# BIT_5.net
KiCad netlist of a schematic drawn in EasyEDA
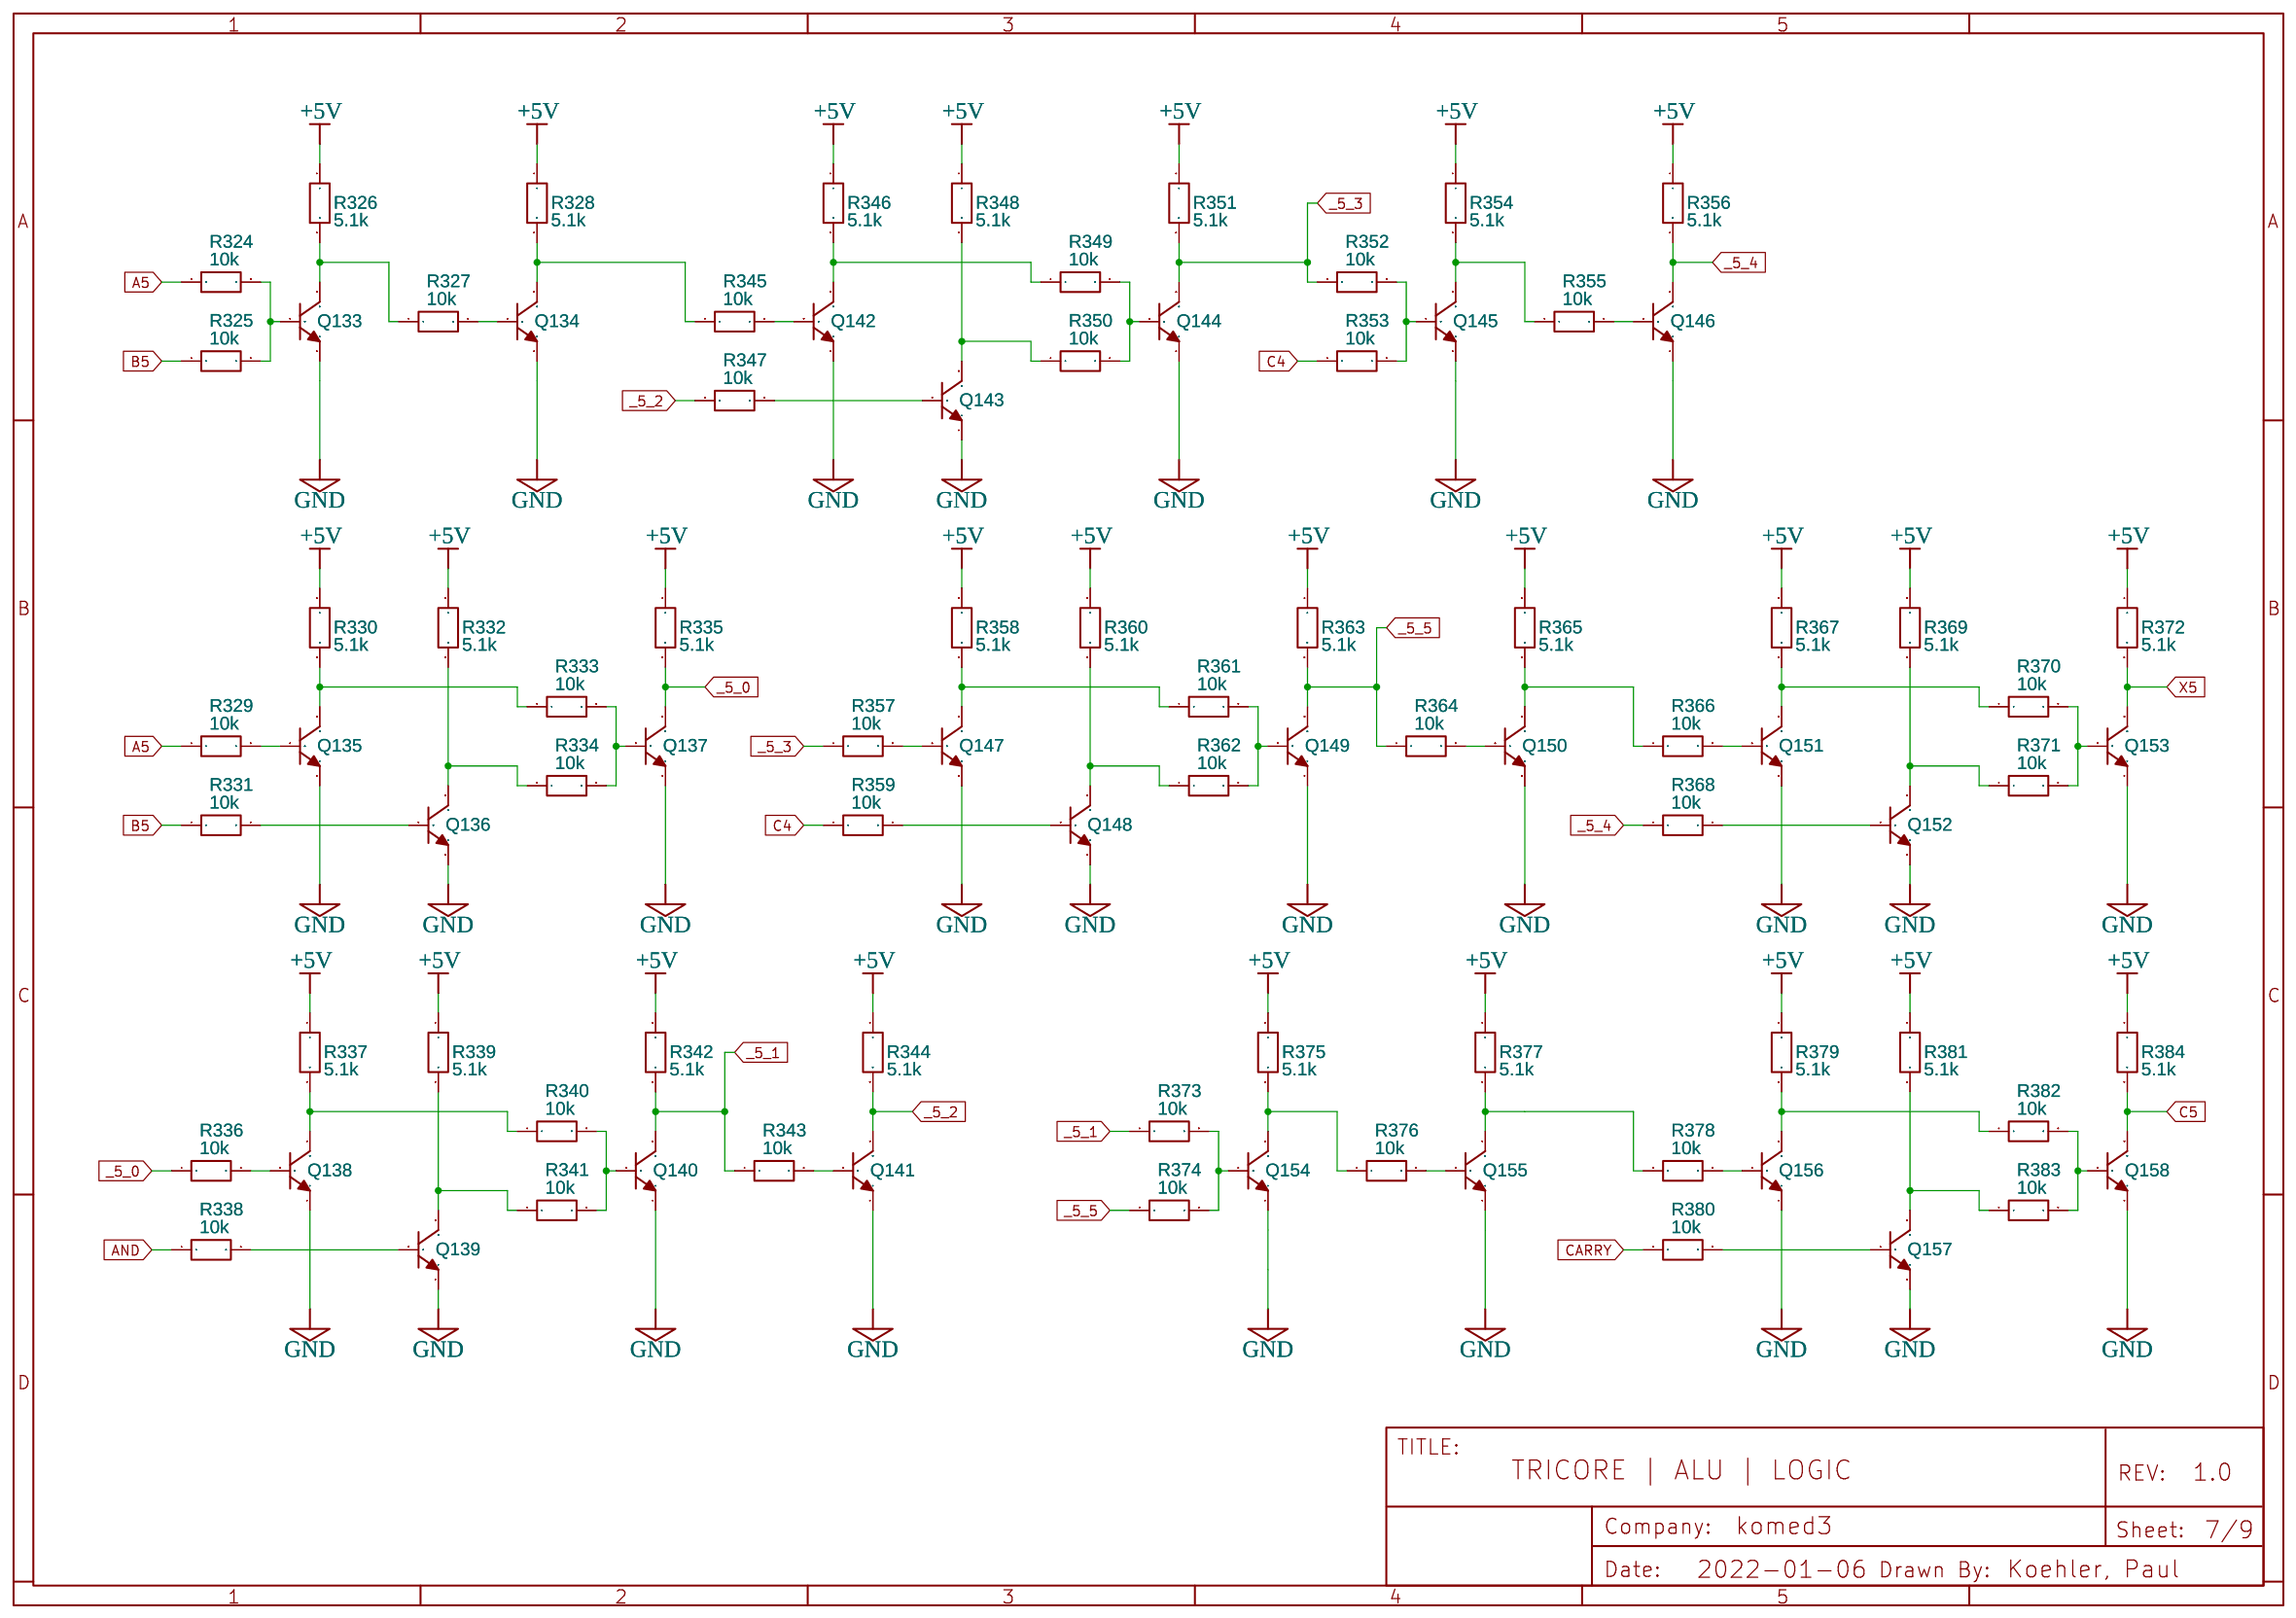
[diagram p0: schematic sheet]

(export (version "E")
  (design (tool "Eeschema 10.0.6"))
  (components
    (comp (ref "Q133")
      (value "2N3904(TO-92)")
      (fields (field (name "BOM_Manufacturer Part") "2N3904") (field (name "BOM_Supplier Part") "C118538"))
      (libsource (lib "") (part "2N3904(TO-92)"))
    )
    (comp (ref "Q134")
      (value "2N3904(TO-92)")
      (fields (field (name "BOM_Manufacturer Part") "2N3904") (field (name "BOM_Supplier Part") "C118538"))
      (libsource (lib "") (part "2N3904(TO-92)"))
    )
    (comp (ref "Q135")
      (value "2N3904(TO-92)")
      (fields (field (name "BOM_Manufacturer Part") "2N3904") (field (name "BOM_Supplier Part") "C118538"))
      (libsource (lib "") (part "2N3904(TO-92)"))
    )
    (comp (ref "Q136")
      (value "2N3904(TO-92)")
      (fields (field (name "BOM_Manufacturer Part") "2N3904") (field (name "BOM_Supplier Part") "C118538"))
      (libsource (lib "") (part "2N3904(TO-92)"))
    )
    (comp (ref "Q137")
      (value "2N3904(TO-92)")
      (fields (field (name "BOM_Manufacturer Part") "2N3904") (field (name "BOM_Supplier Part") "C118538"))
      (libsource (lib "") (part "2N3904(TO-92)"))
    )
    (comp (ref "Q138")
      (value "2N3904(TO-92)")
      (fields (field (name "BOM_Manufacturer Part") "2N3904") (field (name "BOM_Supplier Part") "C118538"))
      (libsource (lib "") (part "2N3904(TO-92)"))
    )
    (comp (ref "Q139")
      (value "2N3904(TO-92)")
      (fields (field (name "BOM_Manufacturer Part") "2N3904") (field (name "BOM_Supplier Part") "C118538"))
      (libsource (lib "") (part "2N3904(TO-92)"))
    )
    (comp (ref "Q140")
      (value "2N3904(TO-92)")
      (fields (field (name "BOM_Manufacturer Part") "2N3904") (field (name "BOM_Supplier Part") "C118538"))
      (libsource (lib "") (part "2N3904(TO-92)"))
    )
    (comp (ref "Q141")
      (value "2N3904(TO-92)")
      (fields (field (name "BOM_Manufacturer Part") "2N3904") (field (name "BOM_Supplier Part") "C118538"))
      (libsource (lib "") (part "2N3904(TO-92)"))
    )
    (comp (ref "Q142")
      (value "2N3904(TO-92)")
      (fields (field (name "BOM_Manufacturer Part") "2N3904") (field (name "BOM_Supplier Part") "C118538"))
      (libsource (lib "") (part "2N3904(TO-92)"))
    )
    (comp (ref "Q143")
      (value "2N3904(TO-92)")
      (fields (field (name "BOM_Manufacturer Part") "2N3904") (field (name "BOM_Supplier Part") "C118538"))
      (libsource (lib "") (part "2N3904(TO-92)"))
    )
    (comp (ref "Q144")
      (value "2N3904(TO-92)")
      (fields (field (name "BOM_Manufacturer Part") "2N3904") (field (name "BOM_Supplier Part") "C118538"))
      (libsource (lib "") (part "2N3904(TO-92)"))
    )
    (comp (ref "Q145")
      (value "2N3904(TO-92)")
      (fields (field (name "BOM_Manufacturer Part") "2N3904") (field (name "BOM_Supplier Part") "C118538"))
      (libsource (lib "") (part "2N3904(TO-92)"))
    )
    (comp (ref "Q146")
      (value "2N3904(TO-92)")
      (fields (field (name "BOM_Manufacturer Part") "2N3904") (field (name "BOM_Supplier Part") "C118538"))
      (libsource (lib "") (part "2N3904(TO-92)"))
    )
    (comp (ref "Q147")
      (value "2N3904(TO-92)")
      (fields (field (name "BOM_Manufacturer Part") "2N3904") (field (name "BOM_Supplier Part") "C118538"))
      (libsource (lib "") (part "2N3904(TO-92)"))
    )
    (comp (ref "Q148")
      (value "2N3904(TO-92)")
      (fields (field (name "BOM_Manufacturer Part") "2N3904") (field (name "BOM_Supplier Part") "C118538"))
      (libsource (lib "") (part "2N3904(TO-92)"))
    )
    (comp (ref "Q149")
      (value "2N3904(TO-92)")
      (fields (field (name "BOM_Manufacturer Part") "2N3904") (field (name "BOM_Supplier Part") "C118538"))
      (libsource (lib "") (part "2N3904(TO-92)"))
    )
    (comp (ref "Q150")
      (value "2N3904(TO-92)")
      (fields (field (name "BOM_Manufacturer Part") "2N3904") (field (name "BOM_Supplier Part") "C118538"))
      (libsource (lib "") (part "2N3904(TO-92)"))
    )
    (comp (ref "Q151")
      (value "2N3904(TO-92)")
      (fields (field (name "BOM_Manufacturer Part") "2N3904") (field (name "BOM_Supplier Part") "C118538"))
      (libsource (lib "") (part "2N3904(TO-92)"))
    )
    (comp (ref "Q152")
      (value "2N3904(TO-92)")
      (fields (field (name "BOM_Manufacturer Part") "2N3904") (field (name "BOM_Supplier Part") "C118538"))
      (libsource (lib "") (part "2N3904(TO-92)"))
    )
    (comp (ref "Q153")
      (value "2N3904(TO-92)")
      (fields (field (name "BOM_Manufacturer Part") "2N3904") (field (name "BOM_Supplier Part") "C118538"))
      (libsource (lib "") (part "2N3904(TO-92)"))
    )
    (comp (ref "Q154")
      (value "2N3904(TO-92)")
      (fields (field (name "BOM_Manufacturer Part") "2N3904") (field (name "BOM_Supplier Part") "C118538"))
      (libsource (lib "") (part "2N3904(TO-92)"))
    )
    (comp (ref "Q155")
      (value "2N3904(TO-92)")
      (fields (field (name "BOM_Manufacturer Part") "2N3904") (field (name "BOM_Supplier Part") "C118538"))
      (libsource (lib "") (part "2N3904(TO-92)"))
    )
    (comp (ref "Q156")
      (value "2N3904(TO-92)")
      (fields (field (name "BOM_Manufacturer Part") "2N3904") (field (name "BOM_Supplier Part") "C118538"))
      (libsource (lib "") (part "2N3904(TO-92)"))
    )
    (comp (ref "Q157")
      (value "2N3904(TO-92)")
      (fields (field (name "BOM_Manufacturer Part") "2N3904") (field (name "BOM_Supplier Part") "C118538"))
      (libsource (lib "") (part "2N3904(TO-92)"))
    )
    (comp (ref "Q158")
      (value "2N3904(TO-92)")
      (fields (field (name "BOM_Manufacturer Part") "2N3904") (field (name "BOM_Supplier Part") "C118538"))
      (libsource (lib "") (part "2N3904(TO-92)"))
    )
    (comp (ref "R324") (value "10k") (libsource (lib "") (part "R_AXIAL-0.3_EU")))
    (comp (ref "R325") (value "10k") (libsource (lib "") (part "R_AXIAL-0.3_EU")))
    (comp (ref "R326") (value "5.1k") (libsource (lib "") (part "R_AXIAL-0.3_EU_1")))
    (comp (ref "R327") (value "10k") (libsource (lib "") (part "R_AXIAL-0.3_EU")))
    (comp (ref "R328") (value "5.1k") (libsource (lib "") (part "R_AXIAL-0.3_EU_1")))
    (comp (ref "R329") (value "10k") (libsource (lib "") (part "R_AXIAL-0.3_EU")))
    (comp (ref "R330") (value "5.1k") (libsource (lib "") (part "R_AXIAL-0.3_EU_1")))
    (comp (ref "R331") (value "10k") (libsource (lib "") (part "R_AXIAL-0.3_EU")))
    (comp (ref "R332") (value "5.1k") (libsource (lib "") (part "R_AXIAL-0.3_EU_1")))
    (comp (ref "R333") (value "10k") (libsource (lib "") (part "R_AXIAL-0.3_EU")))
    (comp (ref "R334") (value "10k") (libsource (lib "") (part "R_AXIAL-0.3_EU")))
    (comp (ref "R335") (value "5.1k") (libsource (lib "") (part "R_AXIAL-0.3_EU_1")))
    (comp (ref "R336") (value "10k") (libsource (lib "") (part "R_AXIAL-0.3_EU")))
    (comp (ref "R337") (value "5.1k") (libsource (lib "") (part "R_AXIAL-0.3_EU_1")))
    (comp (ref "R338") (value "10k") (libsource (lib "") (part "R_AXIAL-0.3_EU")))
    (comp (ref "R339") (value "5.1k") (libsource (lib "") (part "R_AXIAL-0.3_EU_1")))
    (comp (ref "R340") (value "10k") (libsource (lib "") (part "R_AXIAL-0.3_EU")))
    (comp (ref "R341") (value "10k") (libsource (lib "") (part "R_AXIAL-0.3_EU")))
    (comp (ref "R342") (value "5.1k") (libsource (lib "") (part "R_AXIAL-0.3_EU_1")))
    (comp (ref "R343") (value "10k") (libsource (lib "") (part "R_AXIAL-0.3_EU")))
    (comp (ref "R344") (value "5.1k") (libsource (lib "") (part "R_AXIAL-0.3_EU_1")))
    (comp (ref "R345") (value "10k") (libsource (lib "") (part "R_AXIAL-0.3_EU")))
    (comp (ref "R346") (value "5.1k") (libsource (lib "") (part "R_AXIAL-0.3_EU_1")))
    (comp (ref "R347") (value "10k") (libsource (lib "") (part "R_AXIAL-0.3_EU")))
    (comp (ref "R348") (value "5.1k") (libsource (lib "") (part "R_AXIAL-0.3_EU_1")))
    (comp (ref "R349") (value "10k") (libsource (lib "") (part "R_AXIAL-0.3_EU")))
    (comp (ref "R350") (value "10k") (libsource (lib "") (part "R_AXIAL-0.3_EU")))
    (comp (ref "R351") (value "5.1k") (libsource (lib "") (part "R_AXIAL-0.3_EU_1")))
    (comp (ref "R352") (value "10k") (libsource (lib "") (part "R_AXIAL-0.3_EU")))
    (comp (ref "R353") (value "10k") (libsource (lib "") (part "R_AXIAL-0.3_EU")))
    (comp (ref "R354") (value "5.1k") (libsource (lib "") (part "R_AXIAL-0.3_EU_1")))
    (comp (ref "R355") (value "10k") (libsource (lib "") (part "R_AXIAL-0.3_EU")))
    (comp (ref "R356") (value "5.1k") (libsource (lib "") (part "R_AXIAL-0.3_EU_1")))
    (comp (ref "R357") (value "10k") (libsource (lib "") (part "R_AXIAL-0.3_EU")))
    (comp (ref "R358") (value "5.1k") (libsource (lib "") (part "R_AXIAL-0.3_EU_1")))
    (comp (ref "R359") (value "10k") (libsource (lib "") (part "R_AXIAL-0.3_EU")))
    (comp (ref "R360") (value "5.1k") (libsource (lib "") (part "R_AXIAL-0.3_EU_1")))
    (comp (ref "R361") (value "10k") (libsource (lib "") (part "R_AXIAL-0.3_EU")))
    (comp (ref "R362") (value "10k") (libsource (lib "") (part "R_AXIAL-0.3_EU")))
    (comp (ref "R363") (value "5.1k") (libsource (lib "") (part "R_AXIAL-0.3_EU_1")))
    (comp (ref "R364") (value "10k") (libsource (lib "") (part "R_AXIAL-0.3_EU")))
    (comp (ref "R365") (value "5.1k") (libsource (lib "") (part "R_AXIAL-0.3_EU_1")))
    (comp (ref "R366") (value "10k") (libsource (lib "") (part "R_AXIAL-0.3_EU")))
    (comp (ref "R367") (value "5.1k") (libsource (lib "") (part "R_AXIAL-0.3_EU_1")))
    (comp (ref "R368") (value "10k") (libsource (lib "") (part "R_AXIAL-0.3_EU")))
    (comp (ref "R369") (value "5.1k") (libsource (lib "") (part "R_AXIAL-0.3_EU_1")))
    (comp (ref "R370") (value "10k") (libsource (lib "") (part "R_AXIAL-0.3_EU")))
    (comp (ref "R371") (value "10k") (libsource (lib "") (part "R_AXIAL-0.3_EU")))
    (comp (ref "R372") (value "5.1k") (libsource (lib "") (part "R_AXIAL-0.3_EU_1")))
    (comp (ref "R373") (value "10k") (libsource (lib "") (part "R_AXIAL-0.3_EU")))
    (comp (ref "R374") (value "10k") (libsource (lib "") (part "R_AXIAL-0.3_EU")))
    (comp (ref "R375") (value "5.1k") (libsource (lib "") (part "R_AXIAL-0.3_EU_1")))
    (comp (ref "R376") (value "10k") (libsource (lib "") (part "R_AXIAL-0.3_EU")))
    (comp (ref "R377") (value "5.1k") (libsource (lib "") (part "R_AXIAL-0.3_EU_1")))
    (comp (ref "R378") (value "10k") (libsource (lib "") (part "R_AXIAL-0.3_EU")))
    (comp (ref "R379") (value "5.1k") (libsource (lib "") (part "R_AXIAL-0.3_EU_1")))
    (comp (ref "R380") (value "10k") (libsource (lib "") (part "R_AXIAL-0.3_EU")))
    (comp (ref "R381") (value "5.1k") (libsource (lib "") (part "R_AXIAL-0.3_EU_1")))
    (comp (ref "R382") (value "10k") (libsource (lib "") (part "R_AXIAL-0.3_EU")))
    (comp (ref "R383") (value "10k") (libsource (lib "") (part "R_AXIAL-0.3_EU")))
    (comp (ref "R384") (value "5.1k") (libsource (lib "") (part "R_AXIAL-0.3_EU_1")))
  )
  (nets
    (net (code "1") (name "+5V") (class "Default")
      (node (ref "R326") (pin "1") (pinfunction "1_1") (pintype "unspecified"))
      (node (ref "R328") (pin "1") (pinfunction "1_1") (pintype "unspecified"))
      (node (ref "R330") (pin "1") (pinfunction "1_1") (pintype "unspecified"))
      (node (ref "R332") (pin "1") (pinfunction "1_1") (pintype "unspecified"))
      (node (ref "R335") (pin "1") (pinfunction "1_1") (pintype "unspecified"))
      (node (ref "R337") (pin "1") (pinfunction "1_1") (pintype "unspecified"))
      (node (ref "R339") (pin "1") (pinfunction "1_1") (pintype "unspecified"))
      (node (ref "R342") (pin "1") (pinfunction "1_1") (pintype "unspecified"))
      (node (ref "R344") (pin "1") (pinfunction "1_1") (pintype "unspecified"))
      (node (ref "R346") (pin "1") (pinfunction "1_1") (pintype "unspecified"))
      (node (ref "R348") (pin "1") (pinfunction "1_1") (pintype "unspecified"))
      (node (ref "R351") (pin "1") (pinfunction "1_1") (pintype "unspecified"))
      (node (ref "R354") (pin "1") (pinfunction "1_1") (pintype "unspecified"))
      (node (ref "R356") (pin "1") (pinfunction "1_1") (pintype "unspecified"))
      (node (ref "R358") (pin "1") (pinfunction "1_1") (pintype "unspecified"))
      (node (ref "R360") (pin "1") (pinfunction "1_1") (pintype "unspecified"))
      (node (ref "R363") (pin "1") (pinfunction "1_1") (pintype "unspecified"))
      (node (ref "R365") (pin "1") (pinfunction "1_1") (pintype "unspecified"))
      (node (ref "R367") (pin "1") (pinfunction "1_1") (pintype "unspecified"))
      (node (ref "R369") (pin "1") (pinfunction "1_1") (pintype "unspecified"))
      (node (ref "R372") (pin "1") (pinfunction "1_1") (pintype "unspecified"))
      (node (ref "R375") (pin "1") (pinfunction "1_1") (pintype "unspecified"))
      (node (ref "R377") (pin "1") (pinfunction "1_1") (pintype "unspecified"))
      (node (ref "R379") (pin "1") (pinfunction "1_1") (pintype "unspecified"))
      (node (ref "R381") (pin "1") (pinfunction "1_1") (pintype "unspecified"))
      (node (ref "R384") (pin "1") (pinfunction "1_1") (pintype "unspecified"))
    )
    (net (code "2") (name "A5") (class "Default")
      (node (ref "R324") (pin "1") (pinfunction "1_1") (pintype "unspecified"))
      (node (ref "R329") (pin "1") (pinfunction "1_1") (pintype "unspecified"))
    )
    (net (code "3") (name "AND") (class "Default")
      (node (ref "R338") (pin "1") (pinfunction "1_1") (pintype "unspecified"))
    )
    (net (code "4") (name "B5") (class "Default")
      (node (ref "R325") (pin "1") (pinfunction "1_1") (pintype "unspecified"))
      (node (ref "R331") (pin "1") (pinfunction "1_1") (pintype "unspecified"))
    )
    (net (code "5") (name "C4") (class "Default")
      (node (ref "R353") (pin "1") (pinfunction "1_1") (pintype "unspecified"))
      (node (ref "R359") (pin "1") (pinfunction "1_1") (pintype "unspecified"))
    )
    (net (code "6") (name "C5") (class "Default")
      (node (ref "Q158") (pin "3") (pinfunction "C_3") (pintype "unspecified"))
      (node (ref "R384") (pin "2") (pinfunction "2_2") (pintype "unspecified"))
    )
    (net (code "7") (name "CARRY") (class "Default")
      (node (ref "R380") (pin "1") (pinfunction "1_1") (pintype "unspecified"))
    )
    (net (code "8") (name "GND") (class "Default")
      (node (ref "Q133") (pin "1") (pinfunction "E_1") (pintype "unspecified"))
      (node (ref "Q134") (pin "1") (pinfunction "E_1") (pintype "unspecified"))
      (node (ref "Q135") (pin "1") (pinfunction "E_1") (pintype "unspecified"))
      (node (ref "Q136") (pin "1") (pinfunction "E_1") (pintype "unspecified"))
      (node (ref "Q137") (pin "1") (pinfunction "E_1") (pintype "unspecified"))
      (node (ref "Q138") (pin "1") (pinfunction "E_1") (pintype "unspecified"))
      (node (ref "Q139") (pin "1") (pinfunction "E_1") (pintype "unspecified"))
      (node (ref "Q140") (pin "1") (pinfunction "E_1") (pintype "unspecified"))
      (node (ref "Q141") (pin "1") (pinfunction "E_1") (pintype "unspecified"))
      (node (ref "Q142") (pin "1") (pinfunction "E_1") (pintype "unspecified"))
      (node (ref "Q143") (pin "1") (pinfunction "E_1") (pintype "unspecified"))
      (node (ref "Q144") (pin "1") (pinfunction "E_1") (pintype "unspecified"))
      (node (ref "Q145") (pin "1") (pinfunction "E_1") (pintype "unspecified"))
      (node (ref "Q146") (pin "1") (pinfunction "E_1") (pintype "unspecified"))
      (node (ref "Q147") (pin "1") (pinfunction "E_1") (pintype "unspecified"))
      (node (ref "Q148") (pin "1") (pinfunction "E_1") (pintype "unspecified"))
      (node (ref "Q149") (pin "1") (pinfunction "E_1") (pintype "unspecified"))
      (node (ref "Q150") (pin "1") (pinfunction "E_1") (pintype "unspecified"))
      (node (ref "Q151") (pin "1") (pinfunction "E_1") (pintype "unspecified"))
      (node (ref "Q152") (pin "1") (pinfunction "E_1") (pintype "unspecified"))
      (node (ref "Q153") (pin "1") (pinfunction "E_1") (pintype "unspecified"))
      (node (ref "Q154") (pin "1") (pinfunction "E_1") (pintype "unspecified"))
      (node (ref "Q155") (pin "1") (pinfunction "E_1") (pintype "unspecified"))
      (node (ref "Q156") (pin "1") (pinfunction "E_1") (pintype "unspecified"))
      (node (ref "Q157") (pin "1") (pinfunction "E_1") (pintype "unspecified"))
      (node (ref "Q158") (pin "1") (pinfunction "E_1") (pintype "unspecified"))
    )
    (net (code "9") (name "Net-(Q133-B)") (class "Default")
      (node (ref "Q133") (pin "2") (pinfunction "B_2") (pintype "unspecified"))
      (node (ref "R324") (pin "2") (pinfunction "2_2") (pintype "unspecified"))
      (node (ref "R325") (pin "2") (pinfunction "2_2") (pintype "unspecified"))
    )
    (net (code "10") (name "Net-(Q133-C)") (class "Default")
      (node (ref "Q133") (pin "3") (pinfunction "C_3") (pintype "unspecified"))
      (node (ref "R326") (pin "2") (pinfunction "2_2") (pintype "unspecified"))
      (node (ref "R327") (pin "1") (pinfunction "1_1") (pintype "unspecified"))
    )
    (net (code "11") (name "Net-(Q134-B)") (class "Default")
      (node (ref "Q134") (pin "2") (pinfunction "B_2") (pintype "unspecified"))
      (node (ref "R327") (pin "2") (pinfunction "2_2") (pintype "unspecified"))
    )
    (net (code "12") (name "Net-(Q134-C)") (class "Default")
      (node (ref "Q134") (pin "3") (pinfunction "C_3") (pintype "unspecified"))
      (node (ref "R328") (pin "2") (pinfunction "2_2") (pintype "unspecified"))
      (node (ref "R345") (pin "1") (pinfunction "1_1") (pintype "unspecified"))
    )
    (net (code "13") (name "Net-(Q135-B)") (class "Default")
      (node (ref "Q135") (pin "2") (pinfunction "B_2") (pintype "unspecified"))
      (node (ref "R329") (pin "2") (pinfunction "2_2") (pintype "unspecified"))
    )
    (net (code "14") (name "Net-(Q135-C)") (class "Default")
      (node (ref "Q135") (pin "3") (pinfunction "C_3") (pintype "unspecified"))
      (node (ref "R330") (pin "2") (pinfunction "2_2") (pintype "unspecified"))
      (node (ref "R333") (pin "1") (pinfunction "1_1") (pintype "unspecified"))
    )
    (net (code "15") (name "Net-(Q136-B)") (class "Default")
      (node (ref "Q136") (pin "2") (pinfunction "B_2") (pintype "unspecified"))
      (node (ref "R331") (pin "2") (pinfunction "2_2") (pintype "unspecified"))
    )
    (net (code "16") (name "Net-(Q136-C)") (class "Default")
      (node (ref "Q136") (pin "3") (pinfunction "C_3") (pintype "unspecified"))
      (node (ref "R332") (pin "2") (pinfunction "2_2") (pintype "unspecified"))
      (node (ref "R334") (pin "1") (pinfunction "1_1") (pintype "unspecified"))
    )
    (net (code "17") (name "Net-(Q137-B)") (class "Default")
      (node (ref "Q137") (pin "2") (pinfunction "B_2") (pintype "unspecified"))
      (node (ref "R333") (pin "2") (pinfunction "2_2") (pintype "unspecified"))
      (node (ref "R334") (pin "2") (pinfunction "2_2") (pintype "unspecified"))
    )
    (net (code "18") (name "Net-(Q138-B)") (class "Default")
      (node (ref "Q138") (pin "2") (pinfunction "B_2") (pintype "unspecified"))
      (node (ref "R336") (pin "2") (pinfunction "2_2") (pintype "unspecified"))
    )
    (net (code "19") (name "Net-(Q138-C)") (class "Default")
      (node (ref "Q138") (pin "3") (pinfunction "C_3") (pintype "unspecified"))
      (node (ref "R337") (pin "2") (pinfunction "2_2") (pintype "unspecified"))
      (node (ref "R340") (pin "1") (pinfunction "1_1") (pintype "unspecified"))
    )
    (net (code "20") (name "Net-(Q139-B)") (class "Default")
      (node (ref "Q139") (pin "2") (pinfunction "B_2") (pintype "unspecified"))
      (node (ref "R338") (pin "2") (pinfunction "2_2") (pintype "unspecified"))
    )
    (net (code "21") (name "Net-(Q139-C)") (class "Default")
      (node (ref "Q139") (pin "3") (pinfunction "C_3") (pintype "unspecified"))
      (node (ref "R339") (pin "2") (pinfunction "2_2") (pintype "unspecified"))
      (node (ref "R341") (pin "1") (pinfunction "1_1") (pintype "unspecified"))
    )
    (net (code "22") (name "Net-(Q140-B)") (class "Default")
      (node (ref "Q140") (pin "2") (pinfunction "B_2") (pintype "unspecified"))
      (node (ref "R340") (pin "2") (pinfunction "2_2") (pintype "unspecified"))
      (node (ref "R341") (pin "2") (pinfunction "2_2") (pintype "unspecified"))
    )
    (net (code "23") (name "Net-(Q141-B)") (class "Default")
      (node (ref "Q141") (pin "2") (pinfunction "B_2") (pintype "unspecified"))
      (node (ref "R343") (pin "2") (pinfunction "2_2") (pintype "unspecified"))
    )
    (net (code "24") (name "Net-(Q142-B)") (class "Default")
      (node (ref "Q142") (pin "2") (pinfunction "B_2") (pintype "unspecified"))
      (node (ref "R345") (pin "2") (pinfunction "2_2") (pintype "unspecified"))
    )
    (net (code "25") (name "Net-(Q142-C)") (class "Default")
      (node (ref "Q142") (pin "3") (pinfunction "C_3") (pintype "unspecified"))
      (node (ref "R346") (pin "2") (pinfunction "2_2") (pintype "unspecified"))
      (node (ref "R349") (pin "1") (pinfunction "1_1") (pintype "unspecified"))
    )
    (net (code "26") (name "Net-(Q143-B)") (class "Default")
      (node (ref "Q143") (pin "2") (pinfunction "B_2") (pintype "unspecified"))
      (node (ref "R347") (pin "2") (pinfunction "2_2") (pintype "unspecified"))
    )
    (net (code "27") (name "Net-(Q143-C)") (class "Default")
      (node (ref "Q143") (pin "3") (pinfunction "C_3") (pintype "unspecified"))
      (node (ref "R348") (pin "2") (pinfunction "2_2") (pintype "unspecified"))
      (node (ref "R350") (pin "1") (pinfunction "1_1") (pintype "unspecified"))
    )
    (net (code "28") (name "Net-(Q144-B)") (class "Default")
      (node (ref "Q144") (pin "2") (pinfunction "B_2") (pintype "unspecified"))
      (node (ref "R349") (pin "2") (pinfunction "2_2") (pintype "unspecified"))
      (node (ref "R350") (pin "2") (pinfunction "2_2") (pintype "unspecified"))
    )
    (net (code "29") (name "Net-(Q145-B)") (class "Default")
      (node (ref "Q145") (pin "2") (pinfunction "B_2") (pintype "unspecified"))
      (node (ref "R352") (pin "2") (pinfunction "2_2") (pintype "unspecified"))
      (node (ref "R353") (pin "2") (pinfunction "2_2") (pintype "unspecified"))
    )
    (net (code "30") (name "Net-(Q145-C)") (class "Default")
      (node (ref "Q145") (pin "3") (pinfunction "C_3") (pintype "unspecified"))
      (node (ref "R354") (pin "2") (pinfunction "2_2") (pintype "unspecified"))
      (node (ref "R355") (pin "1") (pinfunction "1_1") (pintype "unspecified"))
    )
    (net (code "31") (name "Net-(Q146-B)") (class "Default")
      (node (ref "Q146") (pin "2") (pinfunction "B_2") (pintype "unspecified"))
      (node (ref "R355") (pin "2") (pinfunction "2_2") (pintype "unspecified"))
    )
    (net (code "32") (name "Net-(Q147-B)") (class "Default")
      (node (ref "Q147") (pin "2") (pinfunction "B_2") (pintype "unspecified"))
      (node (ref "R357") (pin "2") (pinfunction "2_2") (pintype "unspecified"))
    )
    (net (code "33") (name "Net-(Q147-C)") (class "Default")
      (node (ref "Q147") (pin "3") (pinfunction "C_3") (pintype "unspecified"))
      (node (ref "R358") (pin "2") (pinfunction "2_2") (pintype "unspecified"))
      (node (ref "R361") (pin "1") (pinfunction "1_1") (pintype "unspecified"))
    )
    (net (code "34") (name "Net-(Q148-B)") (class "Default")
      (node (ref "Q148") (pin "2") (pinfunction "B_2") (pintype "unspecified"))
      (node (ref "R359") (pin "2") (pinfunction "2_2") (pintype "unspecified"))
    )
    (net (code "35") (name "Net-(Q148-C)") (class "Default")
      (node (ref "Q148") (pin "3") (pinfunction "C_3") (pintype "unspecified"))
      (node (ref "R360") (pin "2") (pinfunction "2_2") (pintype "unspecified"))
      (node (ref "R362") (pin "1") (pinfunction "1_1") (pintype "unspecified"))
    )
    (net (code "36") (name "Net-(Q149-B)") (class "Default")
      (node (ref "Q149") (pin "2") (pinfunction "B_2") (pintype "unspecified"))
      (node (ref "R361") (pin "2") (pinfunction "2_2") (pintype "unspecified"))
      (node (ref "R362") (pin "2") (pinfunction "2_2") (pintype "unspecified"))
    )
    (net (code "37") (name "Net-(Q150-B)") (class "Default")
      (node (ref "Q150") (pin "2") (pinfunction "B_2") (pintype "unspecified"))
      (node (ref "R364") (pin "2") (pinfunction "2_2") (pintype "unspecified"))
    )
    (net (code "38") (name "Net-(Q150-C)") (class "Default")
      (node (ref "Q150") (pin "3") (pinfunction "C_3") (pintype "unspecified"))
      (node (ref "R365") (pin "2") (pinfunction "2_2") (pintype "unspecified"))
      (node (ref "R366") (pin "1") (pinfunction "1_1") (pintype "unspecified"))
    )
    (net (code "39") (name "Net-(Q151-B)") (class "Default")
      (node (ref "Q151") (pin "2") (pinfunction "B_2") (pintype "unspecified"))
      (node (ref "R366") (pin "2") (pinfunction "2_2") (pintype "unspecified"))
    )
    (net (code "40") (name "Net-(Q151-C)") (class "Default")
      (node (ref "Q151") (pin "3") (pinfunction "C_3") (pintype "unspecified"))
      (node (ref "R367") (pin "2") (pinfunction "2_2") (pintype "unspecified"))
      (node (ref "R370") (pin "1") (pinfunction "1_1") (pintype "unspecified"))
    )
    (net (code "41") (name "Net-(Q152-B)") (class "Default")
      (node (ref "Q152") (pin "2") (pinfunction "B_2") (pintype "unspecified"))
      (node (ref "R368") (pin "2") (pinfunction "2_2") (pintype "unspecified"))
    )
    (net (code "42") (name "Net-(Q152-C)") (class "Default")
      (node (ref "Q152") (pin "3") (pinfunction "C_3") (pintype "unspecified"))
      (node (ref "R369") (pin "2") (pinfunction "2_2") (pintype "unspecified"))
      (node (ref "R371") (pin "1") (pinfunction "1_1") (pintype "unspecified"))
    )
    (net (code "43") (name "Net-(Q153-B)") (class "Default")
      (node (ref "Q153") (pin "2") (pinfunction "B_2") (pintype "unspecified"))
      (node (ref "R370") (pin "2") (pinfunction "2_2") (pintype "unspecified"))
      (node (ref "R371") (pin "2") (pinfunction "2_2") (pintype "unspecified"))
    )
    (net (code "44") (name "Net-(Q154-B)") (class "Default")
      (node (ref "Q154") (pin "2") (pinfunction "B_2") (pintype "unspecified"))
      (node (ref "R373") (pin "2") (pinfunction "2_2") (pintype "unspecified"))
      (node (ref "R374") (pin "2") (pinfunction "2_2") (pintype "unspecified"))
    )
    (net (code "45") (name "Net-(Q154-C)") (class "Default")
      (node (ref "Q154") (pin "3") (pinfunction "C_3") (pintype "unspecified"))
      (node (ref "R375") (pin "2") (pinfunction "2_2") (pintype "unspecified"))
      (node (ref "R376") (pin "1") (pinfunction "1_1") (pintype "unspecified"))
    )
    (net (code "46") (name "Net-(Q155-B)") (class "Default")
      (node (ref "Q155") (pin "2") (pinfunction "B_2") (pintype "unspecified"))
      (node (ref "R376") (pin "2") (pinfunction "2_2") (pintype "unspecified"))
    )
    (net (code "47") (name "Net-(Q155-C)") (class "Default")
      (node (ref "Q155") (pin "3") (pinfunction "C_3") (pintype "unspecified"))
      (node (ref "R377") (pin "2") (pinfunction "2_2") (pintype "unspecified"))
      (node (ref "R378") (pin "1") (pinfunction "1_1") (pintype "unspecified"))
    )
    (net (code "48") (name "Net-(Q156-B)") (class "Default")
      (node (ref "Q156") (pin "2") (pinfunction "B_2") (pintype "unspecified"))
      (node (ref "R378") (pin "2") (pinfunction "2_2") (pintype "unspecified"))
    )
    (net (code "49") (name "Net-(Q156-C)") (class "Default")
      (node (ref "Q156") (pin "3") (pinfunction "C_3") (pintype "unspecified"))
      (node (ref "R379") (pin "2") (pinfunction "2_2") (pintype "unspecified"))
      (node (ref "R382") (pin "1") (pinfunction "1_1") (pintype "unspecified"))
    )
    (net (code "50") (name "Net-(Q157-B)") (class "Default")
      (node (ref "Q157") (pin "2") (pinfunction "B_2") (pintype "unspecified"))
      (node (ref "R380") (pin "2") (pinfunction "2_2") (pintype "unspecified"))
    )
    (net (code "51") (name "Net-(Q157-C)") (class "Default")
      (node (ref "Q157") (pin "3") (pinfunction "C_3") (pintype "unspecified"))
      (node (ref "R381") (pin "2") (pinfunction "2_2") (pintype "unspecified"))
      (node (ref "R383") (pin "1") (pinfunction "1_1") (pintype "unspecified"))
    )
    (net (code "52") (name "Net-(Q158-B)") (class "Default")
      (node (ref "Q158") (pin "2") (pinfunction "B_2") (pintype "unspecified"))
      (node (ref "R382") (pin "2") (pinfunction "2_2") (pintype "unspecified"))
      (node (ref "R383") (pin "2") (pinfunction "2_2") (pintype "unspecified"))
    )
    (net (code "53") (name "X5") (class "Default")
      (node (ref "Q153") (pin "3") (pinfunction "C_3") (pintype "unspecified"))
      (node (ref "R372") (pin "2") (pinfunction "2_2") (pintype "unspecified"))
    )
    (net (code "54") (name "_5_0") (class "Default")
      (node (ref "Q137") (pin "3") (pinfunction "C_3") (pintype "unspecified"))
      (node (ref "R335") (pin "2") (pinfunction "2_2") (pintype "unspecified"))
      (node (ref "R336") (pin "1") (pinfunction "1_1") (pintype "unspecified"))
    )
    (net (code "55") (name "_5_1") (class "Default")
      (node (ref "Q140") (pin "3") (pinfunction "C_3") (pintype "unspecified"))
      (node (ref "R342") (pin "2") (pinfunction "2_2") (pintype "unspecified"))
      (node (ref "R343") (pin "1") (pinfunction "1_1") (pintype "unspecified"))
      (node (ref "R373") (pin "1") (pinfunction "1_1") (pintype "unspecified"))
    )
    (net (code "56") (name "_5_2") (class "Default")
      (node (ref "Q141") (pin "3") (pinfunction "C_3") (pintype "unspecified"))
      (node (ref "R344") (pin "2") (pinfunction "2_2") (pintype "unspecified"))
      (node (ref "R347") (pin "1") (pinfunction "1_1") (pintype "unspecified"))
    )
    (net (code "57") (name "_5_3") (class "Default")
      (node (ref "Q144") (pin "3") (pinfunction "C_3") (pintype "unspecified"))
      (node (ref "R351") (pin "2") (pinfunction "2_2") (pintype "unspecified"))
      (node (ref "R352") (pin "1") (pinfunction "1_1") (pintype "unspecified"))
      (node (ref "R357") (pin "1") (pinfunction "1_1") (pintype "unspecified"))
    )
    (net (code "58") (name "_5_4") (class "Default")
      (node (ref "Q146") (pin "3") (pinfunction "C_3") (pintype "unspecified"))
      (node (ref "R356") (pin "2") (pinfunction "2_2") (pintype "unspecified"))
      (node (ref "R368") (pin "1") (pinfunction "1_1") (pintype "unspecified"))
    )
    (net (code "59") (name "_5_5") (class "Default")
      (node (ref "Q149") (pin "3") (pinfunction "C_3") (pintype "unspecified"))
      (node (ref "R363") (pin "2") (pinfunction "2_2") (pintype "unspecified"))
      (node (ref "R364") (pin "1") (pinfunction "1_1") (pintype "unspecified"))
      (node (ref "R374") (pin "1") (pinfunction "1_1") (pintype "unspecified"))
    )
  )
)
